# sar20-afbr-s50-array-board.net
KiCad netlist of a schematic drawn in Altium Designer
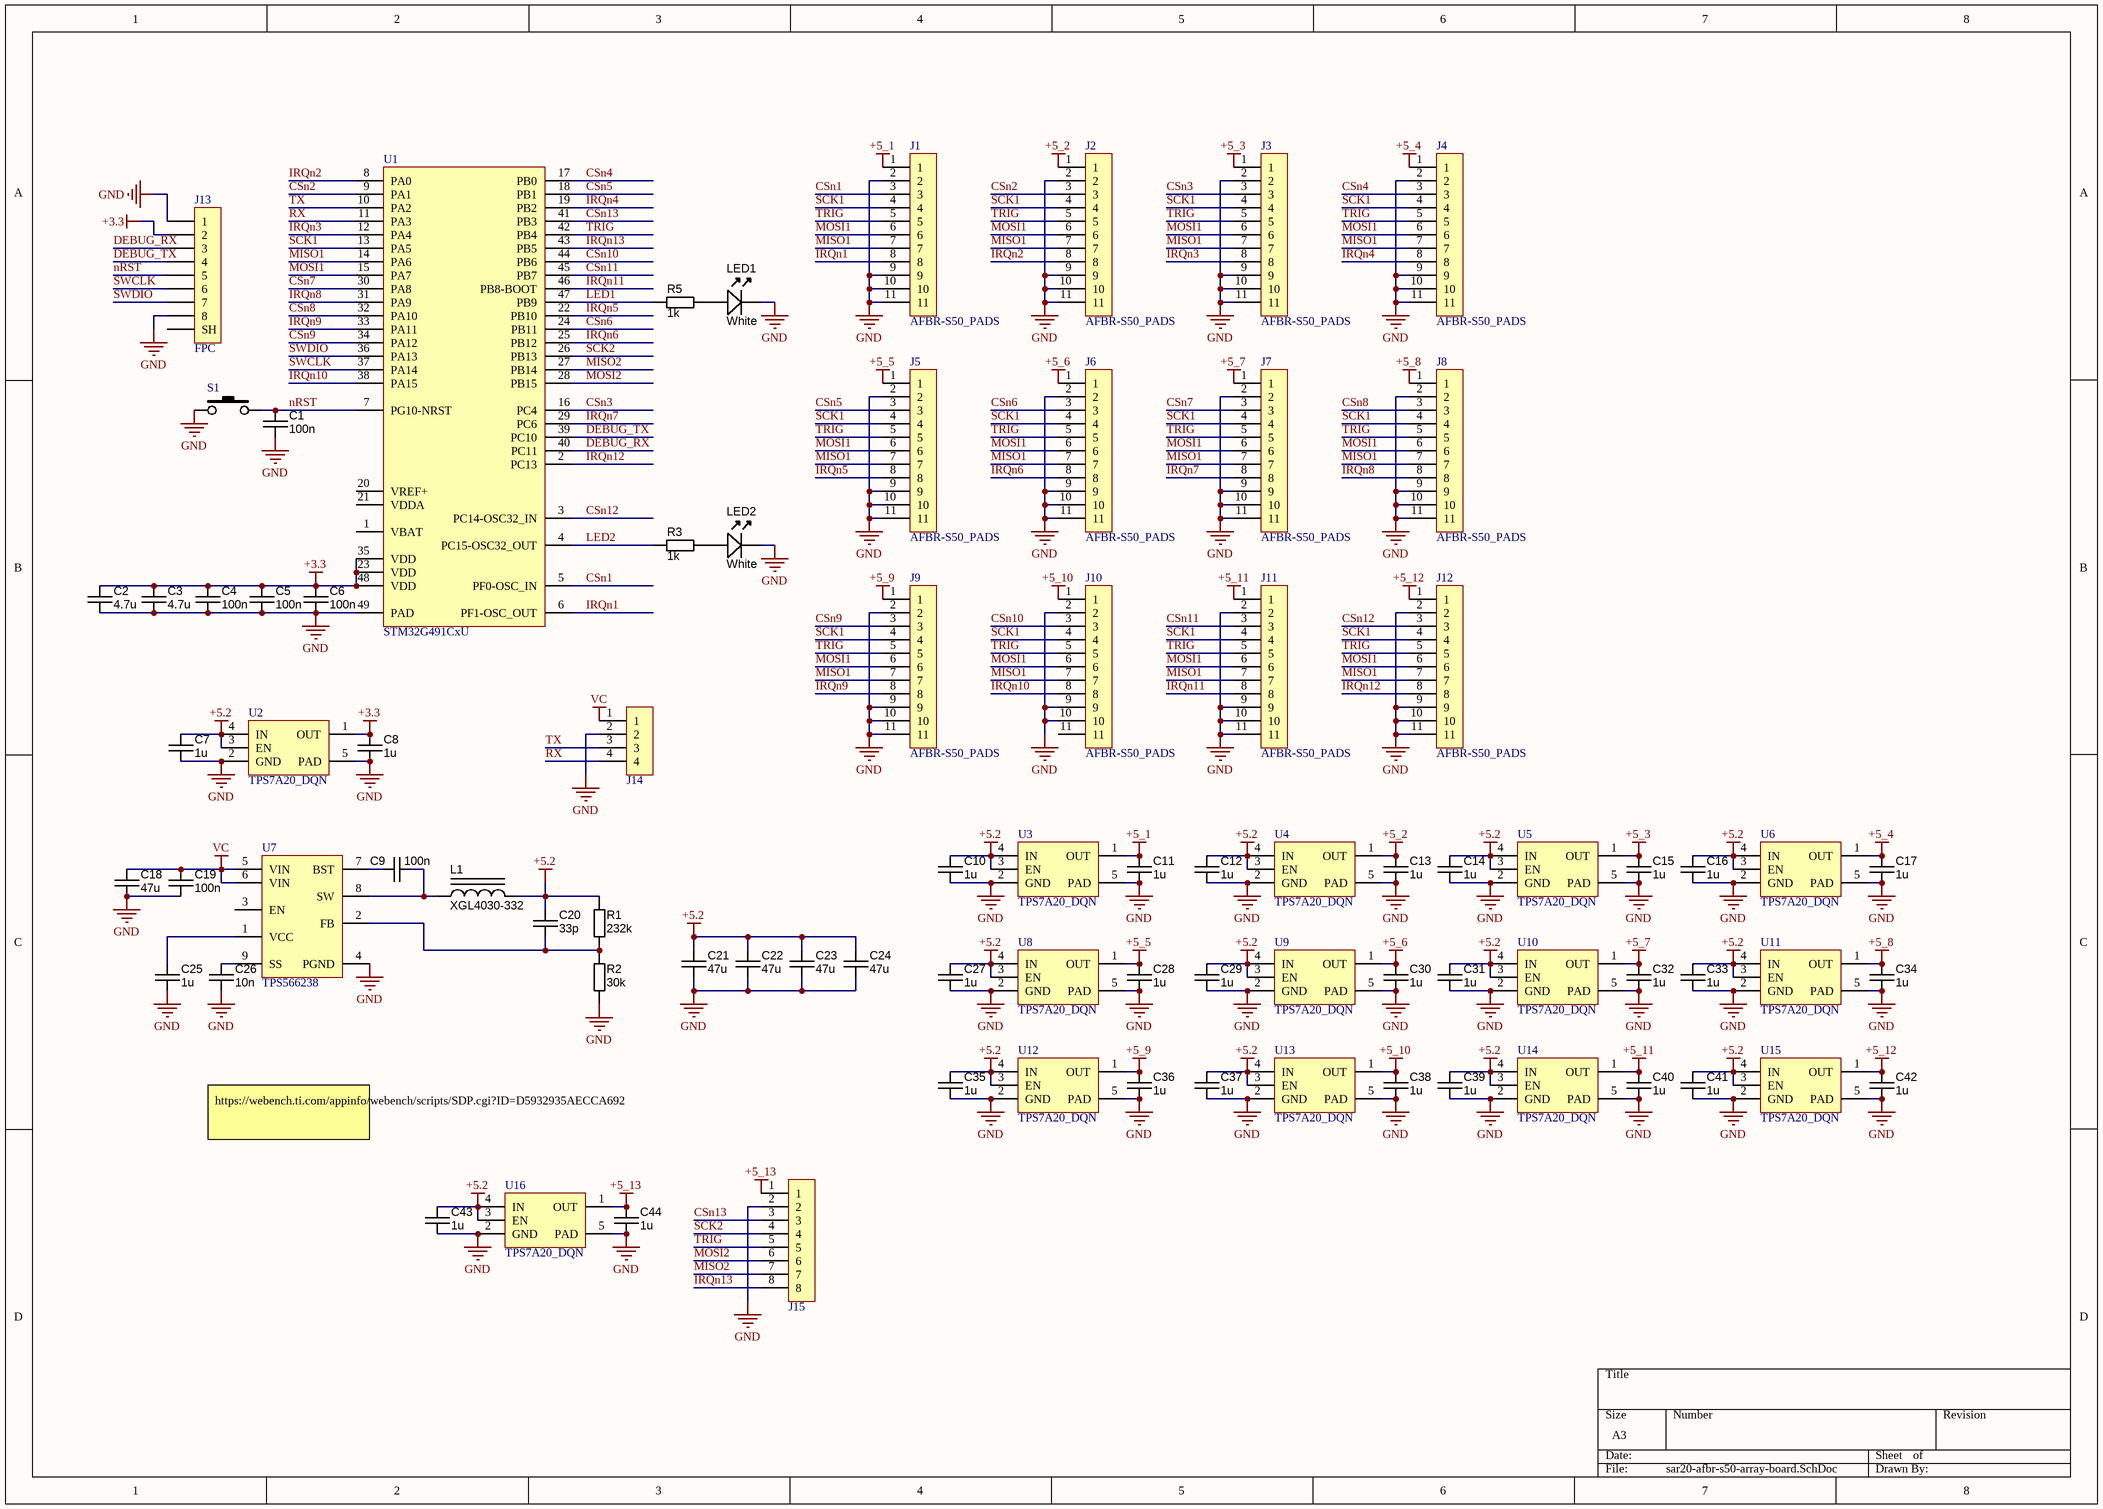
[diagram p0: sar20-afbr-s50-array-board.SchDoc]

(export (version "E")
  (design (tool "Eeschema 10.0.6"))
  (components
    (comp (ref "C1")
      (value "100n")
      (footprint "CAPC0603X04N")
      (fields (field (name "Comment") "CAPC_100n_0201"))
      (libsource (lib "passive") (part "CAPC_100n_0201"))
    )
    (comp (ref "C2")
      (value "4.7u")
      (footprint "CAPC1608X90N")
      (description "Capacitor SMD Cer 2.2uF 10% 10V X5R 0603")
      (fields (field (name "TOLERANCE") "±10%") (field (name "Comment") "approved sub OK"))
      (libsource (lib "PBL - Capacitors") (part "CAPC_2u2_0603_10V_10%"))
    )
    (comp (ref "C3")
      (value "4.7u")
      (footprint "CAPC1608X90N")
      (description "Capacitor SMD Cer 2.2uF 10% 10V X5R 0603")
      (fields (field (name "TOLERANCE") "±10%") (field (name "Comment") "approved sub OK"))
      (libsource (lib "PBL - Capacitors") (part "CAPC_2u2_0603_10V_10%"))
    )
    (comp (ref "C4")
      (value "100n")
      (footprint "CAPC1005X55N")
      (description "Capacitor SMD Cer 100nF 10% 16V X5R 0402")
      (fields (field (name "TOLERANCE") "±10%"))
      (libsource (lib "PBL - Capacitors") (part "CAPC_100n_0402_X5R_16V_10%"))
    )
    (comp (ref "C5")
      (value "100n")
      (footprint "CAPC1005X55N")
      (description "Capacitor SMD Cer 100nF 10% 16V X5R 0402")
      (fields (field (name "TOLERANCE") "±10%"))
      (libsource (lib "PBL - Capacitors") (part "CAPC_100n_0402_X5R_16V_10%"))
    )
    (comp (ref "C6")
      (value "100n")
      (footprint "CAPC1005X55N")
      (description "Capacitor SMD Cer 100nF 10% 16V X5R 0402")
      (fields (field (name "TOLERANCE") "±10%"))
      (libsource (lib "PBL - Capacitors") (part "CAPC_100n_0402_X5R_16V_10%"))
    )
    (comp (ref "C7")
      (value "1u")
      (footprint "CAPC1005X55N")
      (description "Capacitor SMD Cer 100nF 10% 16V X5R 0402")
      (fields (field (name "TOLERANCE") "±10%"))
      (libsource (lib "PBL - Capacitors") (part "CAPC_100n_0402_X5R_16V_10%"))
    )
    (comp (ref "C8")
      (value "1u")
      (footprint "CAPC1005X55N")
      (description "Capacitor SMD Cer 100nF 10% 16V X5R 0402")
      (fields (field (name "TOLERANCE") "±10%"))
      (libsource (lib "PBL - Capacitors") (part "CAPC_100n_0402_X5R_16V_10%"))
    )
    (comp (ref "C9")
      (value "100n")
      (footprint "CAPC1005X55N")
      (description "Capacitor SMD Cer 100nF 10% 16V X5R 0402")
      (fields (field (name "TOLERANCE") "±10%"))
      (libsource (lib "PBL - Capacitors") (part "CAPC_100n_0402_X5R_16V_10%"))
    )
    (comp (ref "C10")
      (value "1u")
      (footprint "CAPC1005X55N")
      (description "Capacitor SMD Cer 100nF 10% 16V X5R 0402")
      (fields (field (name "TOLERANCE") "±10%"))
      (libsource (lib "PBL - Capacitors") (part "CAPC_100n_0402_X5R_16V_10%"))
    )
    (comp (ref "C11")
      (value "1u")
      (footprint "CAPC1005X55N")
      (description "Capacitor SMD Cer 100nF 10% 16V X5R 0402")
      (fields (field (name "TOLERANCE") "±10%"))
      (libsource (lib "PBL - Capacitors") (part "CAPC_100n_0402_X5R_16V_10%"))
    )
    (comp (ref "C12")
      (value "1u")
      (footprint "CAPC1005X55N")
      (description "Capacitor SMD Cer 100nF 10% 16V X5R 0402")
      (fields (field (name "TOLERANCE") "±10%"))
      (libsource (lib "PBL - Capacitors") (part "CAPC_100n_0402_X5R_16V_10%"))
    )
    (comp (ref "C13")
      (value "1u")
      (footprint "CAPC1005X55N")
      (description "Capacitor SMD Cer 100nF 10% 16V X5R 0402")
      (fields (field (name "TOLERANCE") "±10%"))
      (libsource (lib "PBL - Capacitors") (part "CAPC_100n_0402_X5R_16V_10%"))
    )
    (comp (ref "C14")
      (value "1u")
      (footprint "CAPC1005X55N")
      (description "Capacitor SMD Cer 100nF 10% 16V X5R 0402")
      (fields (field (name "TOLERANCE") "±10%"))
      (libsource (lib "PBL - Capacitors") (part "CAPC_100n_0402_X5R_16V_10%"))
    )
    (comp (ref "C15")
      (value "1u")
      (footprint "CAPC1005X55N")
      (description "Capacitor SMD Cer 100nF 10% 16V X5R 0402")
      (fields (field (name "TOLERANCE") "±10%"))
      (libsource (lib "PBL - Capacitors") (part "CAPC_100n_0402_X5R_16V_10%"))
    )
    (comp (ref "C16")
      (value "1u")
      (footprint "CAPC1005X55N")
      (description "Capacitor SMD Cer 100nF 10% 16V X5R 0402")
      (fields (field (name "TOLERANCE") "±10%"))
      (libsource (lib "PBL - Capacitors") (part "CAPC_100n_0402_X5R_16V_10%"))
    )
    (comp (ref "C17")
      (value "1u")
      (footprint "CAPC1005X55N")
      (description "Capacitor SMD Cer 100nF 10% 16V X5R 0402")
      (fields (field (name "TOLERANCE") "±10%"))
      (libsource (lib "PBL - Capacitors") (part "CAPC_100n_0402_X5R_16V_10%"))
    )
    (comp (ref "C18")
      (value "47u")
      (footprint "CAPC3216X180N")
      (description "Capacitor SMD Cer 10uF 10% 16V X7R 1206")
      (fields (field (name "TOLERANCE") "±10%") (field (name "Comment") "approved sub OK"))
      (libsource (lib "PBL - Capacitors") (part "CAPC_10u_1206_16V"))
    )
    (comp (ref "C19")
      (value "100n")
      (footprint "CAPC1005X55N")
      (description "Capacitor SMD Cer 100nF 10% 16V X5R 0402")
      (fields (field (name "TOLERANCE") "±10%"))
      (libsource (lib "PBL - Capacitors") (part "CAPC_100n_0402_X5R_16V_10%"))
    )
    (comp (ref "C20")
      (value "33p")
      (footprint "CAPC1005X55N")
      (description "Capacitor SMD Cer 100nF 10% 16V X5R 0402")
      (fields (field (name "TOLERANCE") "±10%"))
      (libsource (lib "PBL - Capacitors") (part "CAPC_100n_0402_X5R_16V_10%"))
    )
    (comp (ref "C21")
      (value "47u")
      (footprint "CAPC3216X180N")
      (description "Capacitor SMD Cer 10uF 10% 16V X7R 1206")
      (fields (field (name "TOLERANCE") "±10%") (field (name "Comment") "approved sub OK"))
      (libsource (lib "PBL - Capacitors") (part "CAPC_10u_1206_16V"))
    )
    (comp (ref "C22")
      (value "47u")
      (footprint "CAPC3216X180N")
      (description "Capacitor SMD Cer 10uF 10% 16V X7R 1206")
      (fields (field (name "TOLERANCE") "±10%") (field (name "Comment") "approved sub OK"))
      (libsource (lib "PBL - Capacitors") (part "CAPC_10u_1206_16V"))
    )
    (comp (ref "C23")
      (value "47u")
      (footprint "CAPC3216X180N")
      (description "Capacitor SMD Cer 10uF 10% 16V X7R 1206")
      (fields (field (name "TOLERANCE") "±10%") (field (name "Comment") "approved sub OK"))
      (libsource (lib "PBL - Capacitors") (part "CAPC_10u_1206_16V"))
    )
    (comp (ref "C24")
      (value "47u")
      (footprint "CAPC3216X180N")
      (description "Capacitor SMD Cer 10uF 10% 16V X7R 1206")
      (fields (field (name "TOLERANCE") "±10%") (field (name "Comment") "approved sub OK"))
      (libsource (lib "PBL - Capacitors") (part "CAPC_10u_1206_16V"))
    )
    (comp (ref "C25")
      (value "1u")
      (footprint "CAPC1005X55N")
      (description "Capacitor SMD Cer 100nF 10% 16V X5R 0402")
      (fields (field (name "TOLERANCE") "±10%"))
      (libsource (lib "PBL - Capacitors") (part "CAPC_100n_0402_X5R_16V_10%"))
    )
    (comp (ref "C26")
      (value "10n")
      (footprint "CAPC1005X55N")
      (description "Capacitor SMD Cer 100nF 10% 16V X5R 0402")
      (fields (field (name "TOLERANCE") "±10%"))
      (libsource (lib "PBL - Capacitors") (part "CAPC_100n_0402_X5R_16V_10%"))
    )
    (comp (ref "C27")
      (value "1u")
      (footprint "CAPC1005X55N")
      (description "Capacitor SMD Cer 100nF 10% 16V X5R 0402")
      (fields (field (name "TOLERANCE") "±10%"))
      (libsource (lib "PBL - Capacitors") (part "CAPC_100n_0402_X5R_16V_10%"))
    )
    (comp (ref "C28")
      (value "1u")
      (footprint "CAPC1005X55N")
      (description "Capacitor SMD Cer 100nF 10% 16V X5R 0402")
      (fields (field (name "TOLERANCE") "±10%"))
      (libsource (lib "PBL - Capacitors") (part "CAPC_100n_0402_X5R_16V_10%"))
    )
    (comp (ref "C29")
      (value "1u")
      (footprint "CAPC1005X55N")
      (description "Capacitor SMD Cer 100nF 10% 16V X5R 0402")
      (fields (field (name "TOLERANCE") "±10%"))
      (libsource (lib "PBL - Capacitors") (part "CAPC_100n_0402_X5R_16V_10%"))
    )
    (comp (ref "C30")
      (value "1u")
      (footprint "CAPC1005X55N")
      (description "Capacitor SMD Cer 100nF 10% 16V X5R 0402")
      (fields (field (name "TOLERANCE") "±10%"))
      (libsource (lib "PBL - Capacitors") (part "CAPC_100n_0402_X5R_16V_10%"))
    )
    (comp (ref "C31")
      (value "1u")
      (footprint "CAPC1005X55N")
      (description "Capacitor SMD Cer 100nF 10% 16V X5R 0402")
      (fields (field (name "TOLERANCE") "±10%"))
      (libsource (lib "PBL - Capacitors") (part "CAPC_100n_0402_X5R_16V_10%"))
    )
    (comp (ref "C32")
      (value "1u")
      (footprint "CAPC1005X55N")
      (description "Capacitor SMD Cer 100nF 10% 16V X5R 0402")
      (fields (field (name "TOLERANCE") "±10%"))
      (libsource (lib "PBL - Capacitors") (part "CAPC_100n_0402_X5R_16V_10%"))
    )
    (comp (ref "C33")
      (value "1u")
      (footprint "CAPC1005X55N")
      (description "Capacitor SMD Cer 100nF 10% 16V X5R 0402")
      (fields (field (name "TOLERANCE") "±10%"))
      (libsource (lib "PBL - Capacitors") (part "CAPC_100n_0402_X5R_16V_10%"))
    )
    (comp (ref "C34")
      (value "1u")
      (footprint "CAPC1005X55N")
      (description "Capacitor SMD Cer 100nF 10% 16V X5R 0402")
      (fields (field (name "TOLERANCE") "±10%"))
      (libsource (lib "PBL - Capacitors") (part "CAPC_100n_0402_X5R_16V_10%"))
    )
    (comp (ref "C35")
      (value "1u")
      (footprint "CAPC1005X55N")
      (description "Capacitor SMD Cer 100nF 10% 16V X5R 0402")
      (fields (field (name "TOLERANCE") "±10%"))
      (libsource (lib "PBL - Capacitors") (part "CAPC_100n_0402_X5R_16V_10%"))
    )
    (comp (ref "C36")
      (value "1u")
      (footprint "CAPC1005X55N")
      (description "Capacitor SMD Cer 100nF 10% 16V X5R 0402")
      (fields (field (name "TOLERANCE") "±10%"))
      (libsource (lib "PBL - Capacitors") (part "CAPC_100n_0402_X5R_16V_10%"))
    )
    (comp (ref "C37")
      (value "1u")
      (footprint "CAPC1005X55N")
      (description "Capacitor SMD Cer 100nF 10% 16V X5R 0402")
      (fields (field (name "TOLERANCE") "±10%"))
      (libsource (lib "PBL - Capacitors") (part "CAPC_100n_0402_X5R_16V_10%"))
    )
    (comp (ref "C38")
      (value "1u")
      (footprint "CAPC1005X55N")
      (description "Capacitor SMD Cer 100nF 10% 16V X5R 0402")
      (fields (field (name "TOLERANCE") "±10%"))
      (libsource (lib "PBL - Capacitors") (part "CAPC_100n_0402_X5R_16V_10%"))
    )
    (comp (ref "C39")
      (value "1u")
      (footprint "CAPC1005X55N")
      (description "Capacitor SMD Cer 100nF 10% 16V X5R 0402")
      (fields (field (name "TOLERANCE") "±10%"))
      (libsource (lib "PBL - Capacitors") (part "CAPC_100n_0402_X5R_16V_10%"))
    )
    (comp (ref "C40")
      (value "1u")
      (footprint "CAPC1005X55N")
      (description "Capacitor SMD Cer 100nF 10% 16V X5R 0402")
      (fields (field (name "TOLERANCE") "±10%"))
      (libsource (lib "PBL - Capacitors") (part "CAPC_100n_0402_X5R_16V_10%"))
    )
    (comp (ref "C41")
      (value "1u")
      (footprint "CAPC1005X55N")
      (description "Capacitor SMD Cer 100nF 10% 16V X5R 0402")
      (fields (field (name "TOLERANCE") "±10%"))
      (libsource (lib "PBL - Capacitors") (part "CAPC_100n_0402_X5R_16V_10%"))
    )
    (comp (ref "C42")
      (value "1u")
      (footprint "CAPC1005X55N")
      (description "Capacitor SMD Cer 100nF 10% 16V X5R 0402")
      (fields (field (name "TOLERANCE") "±10%"))
      (libsource (lib "PBL - Capacitors") (part "CAPC_100n_0402_X5R_16V_10%"))
    )
    (comp (ref "C43")
      (value "1u")
      (footprint "CAPC1005X55N")
      (description "Capacitor SMD Cer 100nF 10% 16V X5R 0402")
      (fields (field (name "TOLERANCE") "±10%"))
      (libsource (lib "PBL - Capacitors") (part "CAPC_100n_0402_X5R_16V_10%"))
    )
    (comp (ref "C44")
      (value "1u")
      (footprint "CAPC1005X55N")
      (description "Capacitor SMD Cer 100nF 10% 16V X5R 0402")
      (fields (field (name "TOLERANCE") "±10%"))
      (libsource (lib "PBL - Capacitors") (part "CAPC_100n_0402_X5R_16V_10%"))
    )
    (comp (ref "J1")
      (value "AFBR-S50_PADS")
      (footprint "AFBR-S50_PADS")
      (libsource (lib "sar20-afbr-s50-array-board") (part "AFBR-S50_PADS"))
    )
    (comp (ref "J2")
      (value "AFBR-S50_PADS")
      (footprint "AFBR-S50_PADS")
      (libsource (lib "sar20-afbr-s50-array-board") (part "AFBR-S50_PADS"))
    )
    (comp (ref "J3")
      (value "AFBR-S50_PADS")
      (footprint "AFBR-S50_PADS")
      (libsource (lib "sar20-afbr-s50-array-board") (part "AFBR-S50_PADS"))
    )
    (comp (ref "J4")
      (value "AFBR-S50_PADS")
      (footprint "AFBR-S50_PADS")
      (libsource (lib "sar20-afbr-s50-array-board") (part "AFBR-S50_PADS"))
    )
    (comp (ref "J5")
      (value "AFBR-S50_PADS")
      (footprint "AFBR-S50_PADS")
      (libsource (lib "sar20-afbr-s50-array-board") (part "AFBR-S50_PADS"))
    )
    (comp (ref "J6")
      (value "AFBR-S50_PADS")
      (footprint "AFBR-S50_PADS")
      (libsource (lib "sar20-afbr-s50-array-board") (part "AFBR-S50_PADS"))
    )
    (comp (ref "J7")
      (value "AFBR-S50_PADS")
      (footprint "AFBR-S50_PADS")
      (libsource (lib "sar20-afbr-s50-array-board") (part "AFBR-S50_PADS"))
    )
    (comp (ref "J8")
      (value "AFBR-S50_PADS")
      (footprint "AFBR-S50_PADS")
      (libsource (lib "sar20-afbr-s50-array-board") (part "AFBR-S50_PADS"))
    )
    (comp (ref "J9")
      (value "AFBR-S50_PADS")
      (footprint "AFBR-S50_PADS")
      (libsource (lib "sar20-afbr-s50-array-board") (part "AFBR-S50_PADS"))
    )
    (comp (ref "J10")
      (value "AFBR-S50_PADS")
      (footprint "AFBR-S50_PADS")
      (libsource (lib "sar20-afbr-s50-array-board") (part "AFBR-S50_PADS"))
    )
    (comp (ref "J11")
      (value "AFBR-S50_PADS")
      (footprint "AFBR-S50_PADS")
      (libsource (lib "sar20-afbr-s50-array-board") (part "AFBR-S50_PADS"))
    )
    (comp (ref "J12")
      (value "AFBR-S50_PADS")
      (footprint "AFBR-S50_PADS")
      (libsource (lib "sar20-afbr-s50-array-board") (part "AFBR-S50_PADS"))
    )
    (comp (ref "J13")
      (value "FPC")
      (footprint "HIROSE-FH19C-8S-0.5SH")
      (libsource (lib "connectors") (part "FPC-CONNECTOR-8"))
    )
    (comp (ref "J14")
      (value "MOLEX_PICOBLADE_530470410")
      (footprint "MOLEX_PICOBLADE_530470410")
      (libsource (lib "connectors") (part "MOLEX_PICOBLADE_530470410"))
    )
    (comp (ref "J15")
      (value "MOLEX_PICOBLADE_532610871")
      (footprint "MOLEX_PICOBLADE_532610871")
      (libsource (lib "connectors") (part "MOLEX_PICOBLADE_532610871"))
    )
    (comp (ref "L1") (value "XGL4030-332") (footprint "XGL4030") (libsource (lib "passive") (part "XGL4030")))
    (comp (ref "LED1")
      (value "White")
      (footprint "LED-0603-WHITE")
      (description "LED 0603 SMD Bright White 8700K")
      (libsource (lib "PBL - Light Sources") (part "LED_SMD_White_0603_Bright"))
    )
    (comp (ref "LED2")
      (value "White")
      (footprint "LED-0603-WHITE")
      (description "LED 0603 SMD Bright White 8700K")
      (libsource (lib "PBL - Light Sources") (part "LED_SMD_White_0603_Bright"))
    )
    (comp (ref "R1")
      (value "232k")
      (footprint "RESC1005X40N")
      (description "Resistor SMD chip 10k Ohm 0.063W 1% 0402")
      (fields (field (name "TOLERANCE") "±1%") (field (name "Comment") "Thick Film"))
      (libsource (lib "PBL - Resistors") (part "RES_10K_0402_1%"))
    )
    (comp (ref "R2")
      (value "30k")
      (footprint "RESC1005X40N")
      (description "Resistor SMD chip 10k Ohm 0.063W 1% 0402")
      (fields (field (name "TOLERANCE") "±1%") (field (name "Comment") "Thick Film"))
      (libsource (lib "PBL - Resistors") (part "RES_10K_0402_1%"))
    )
    (comp (ref "R3")
      (value "1k")
      (footprint "RESC1005X40N")
      (description "Resistor SMD chip 1k Ohm 0.063W 5% 0402")
      (fields (field (name "TOLERANCE") "±5%") (field (name "Comment") "Thick Film"))
      (libsource (lib "PBL - Resistors") (part "RES_1K_0402_5%"))
    )
    (comp (ref "R5")
      (value "1k")
      (footprint "RESC1005X40N")
      (description "Resistor SMD chip 1k Ohm 0.063W 5% 0402")
      (fields (field (name "TOLERANCE") "±5%") (field (name "Comment") "Thick Film"))
      (libsource (lib "PBL - Resistors") (part "RES_1K_0402_5%"))
    )
    (comp (ref "S1")
      (value "PUSHBUTTON")
      (footprint "KMR421NGLFS")
      (libsource (lib "switches") (part "PUSHBUTTON"))
    )
    (comp (ref "U1")
      (value "STM32G491CxU")
      (footprint "QFN50P700X700X60_HS-49N")
      (libsource (lib "sar20-afbr-s50-array-board") (part "STM32G491CxU"))
    )
    (comp (ref "U2")
      (value "TPS7A20_DQN")
      (footprint "TI_X2SON_DQN0004A")
      (libsource (lib "texas_instruments") (part "TPS7A20_DQN"))
    )
    (comp (ref "U3")
      (value "TPS7A20_DQN")
      (footprint "TI_X2SON_DQN0004A")
      (libsource (lib "texas_instruments") (part "TPS7A20_DQN"))
    )
    (comp (ref "U4")
      (value "TPS7A20_DQN")
      (footprint "TI_X2SON_DQN0004A")
      (libsource (lib "texas_instruments") (part "TPS7A20_DQN"))
    )
    (comp (ref "U5")
      (value "TPS7A20_DQN")
      (footprint "TI_X2SON_DQN0004A")
      (libsource (lib "texas_instruments") (part "TPS7A20_DQN"))
    )
    (comp (ref "U6")
      (value "TPS7A20_DQN")
      (footprint "TI_X2SON_DQN0004A")
      (libsource (lib "texas_instruments") (part "TPS7A20_DQN"))
    )
    (comp (ref "U7")
      (value "TPS566238")
      (footprint "TI_VQFN-HR_RQF0009A")
      (libsource (lib "texas_instruments") (part "TPS566238"))
    )
    (comp (ref "U8")
      (value "TPS7A20_DQN")
      (footprint "TI_X2SON_DQN0004A")
      (libsource (lib "texas_instruments") (part "TPS7A20_DQN"))
    )
    (comp (ref "U9")
      (value "TPS7A20_DQN")
      (footprint "TI_X2SON_DQN0004A")
      (libsource (lib "texas_instruments") (part "TPS7A20_DQN"))
    )
    (comp (ref "U10")
      (value "TPS7A20_DQN")
      (footprint "TI_X2SON_DQN0004A")
      (libsource (lib "texas_instruments") (part "TPS7A20_DQN"))
    )
    (comp (ref "U11")
      (value "TPS7A20_DQN")
      (footprint "TI_X2SON_DQN0004A")
      (libsource (lib "texas_instruments") (part "TPS7A20_DQN"))
    )
    (comp (ref "U12")
      (value "TPS7A20_DQN")
      (footprint "TI_X2SON_DQN0004A")
      (libsource (lib "texas_instruments") (part "TPS7A20_DQN"))
    )
    (comp (ref "U13")
      (value "TPS7A20_DQN")
      (footprint "TI_X2SON_DQN0004A")
      (libsource (lib "texas_instruments") (part "TPS7A20_DQN"))
    )
    (comp (ref "U14")
      (value "TPS7A20_DQN")
      (footprint "TI_X2SON_DQN0004A")
      (libsource (lib "texas_instruments") (part "TPS7A20_DQN"))
    )
    (comp (ref "U15")
      (value "TPS7A20_DQN")
      (footprint "TI_X2SON_DQN0004A")
      (libsource (lib "texas_instruments") (part "TPS7A20_DQN"))
    )
    (comp (ref "U16")
      (value "TPS7A20_DQN")
      (footprint "TI_X2SON_DQN0004A")
      (libsource (lib "texas_instruments") (part "TPS7A20_DQN"))
    )
  )
  (nets
    (net (code "1") (name "+3.3") (class "Default")
      (node (ref "C2") (pin "1") (pintype "passive"))
      (node (ref "C3") (pin "1") (pintype "passive"))
      (node (ref "C4") (pin "2") (pintype "passive"))
      (node (ref "C5") (pin "2") (pintype "passive"))
      (node (ref "C6") (pin "2") (pintype "passive"))
      (node (ref "C8") (pin "2") (pintype "passive"))
      (node (ref "J13") (pin "2") (pinfunction "2_2") (pintype "passive"))
      (node (ref "U1") (pin "23") (pinfunction "VDD_23") (pintype "passive"))
      (node (ref "U1") (pin "35") (pinfunction "VDD_35") (pintype "passive"))
      (node (ref "U1") (pin "48") (pinfunction "VDD_48") (pintype "passive"))
      (node (ref "U2") (pin "1") (pinfunction "OUT_1") (pintype "passive"))
    )
    (net (code "2") (name "+5.2") (class "Default")
      (node (ref "C10") (pin "2") (pintype "passive"))
      (node (ref "C12") (pin "2") (pintype "passive"))
      (node (ref "C14") (pin "2") (pintype "passive"))
      (node (ref "C16") (pin "2") (pintype "passive"))
      (node (ref "C20") (pin "2") (pintype "passive"))
      (node (ref "C21") (pin "1") (pintype "passive"))
      (node (ref "C22") (pin "1") (pintype "passive"))
      (node (ref "C23") (pin "1") (pintype "passive"))
      (node (ref "C24") (pin "1") (pintype "passive"))
      (node (ref "C27") (pin "2") (pintype "passive"))
      (node (ref "C29") (pin "2") (pintype "passive"))
      (node (ref "C31") (pin "2") (pintype "passive"))
      (node (ref "C33") (pin "2") (pintype "passive"))
      (node (ref "C35") (pin "2") (pintype "passive"))
      (node (ref "C37") (pin "2") (pintype "passive"))
      (node (ref "C39") (pin "2") (pintype "passive"))
      (node (ref "C41") (pin "2") (pintype "passive"))
      (node (ref "C43") (pin "2") (pintype "passive"))
      (node (ref "C7") (pin "2") (pintype "passive"))
      (node (ref "L1") (pin "2") (pinfunction "2_2") (pintype "passive"))
      (node (ref "R1") (pin "2") (pinfunction "2_2") (pintype "passive"))
      (node (ref "U10") (pin "3") (pinfunction "EN_3") (pintype "passive"))
      (node (ref "U10") (pin "4") (pinfunction "IN_4") (pintype "passive"))
      (node (ref "U11") (pin "3") (pinfunction "EN_3") (pintype "passive"))
      (node (ref "U11") (pin "4") (pinfunction "IN_4") (pintype "passive"))
      (node (ref "U12") (pin "3") (pinfunction "EN_3") (pintype "passive"))
      (node (ref "U12") (pin "4") (pinfunction "IN_4") (pintype "passive"))
      (node (ref "U13") (pin "3") (pinfunction "EN_3") (pintype "passive"))
      (node (ref "U13") (pin "4") (pinfunction "IN_4") (pintype "passive"))
      (node (ref "U14") (pin "3") (pinfunction "EN_3") (pintype "passive"))
      (node (ref "U14") (pin "4") (pinfunction "IN_4") (pintype "passive"))
      (node (ref "U15") (pin "3") (pinfunction "EN_3") (pintype "passive"))
      (node (ref "U15") (pin "4") (pinfunction "IN_4") (pintype "passive"))
      (node (ref "U16") (pin "3") (pinfunction "EN_3") (pintype "passive"))
      (node (ref "U16") (pin "4") (pinfunction "IN_4") (pintype "passive"))
      (node (ref "U2") (pin "3") (pinfunction "EN_3") (pintype "passive"))
      (node (ref "U2") (pin "4") (pinfunction "IN_4") (pintype "passive"))
      (node (ref "U3") (pin "3") (pinfunction "EN_3") (pintype "passive"))
      (node (ref "U3") (pin "4") (pinfunction "IN_4") (pintype "passive"))
      (node (ref "U4") (pin "3") (pinfunction "EN_3") (pintype "passive"))
      (node (ref "U4") (pin "4") (pinfunction "IN_4") (pintype "passive"))
      (node (ref "U5") (pin "3") (pinfunction "EN_3") (pintype "passive"))
      (node (ref "U5") (pin "4") (pinfunction "IN_4") (pintype "passive"))
      (node (ref "U6") (pin "3") (pinfunction "EN_3") (pintype "passive"))
      (node (ref "U6") (pin "4") (pinfunction "IN_4") (pintype "passive"))
      (node (ref "U8") (pin "3") (pinfunction "EN_3") (pintype "passive"))
      (node (ref "U8") (pin "4") (pinfunction "IN_4") (pintype "passive"))
      (node (ref "U9") (pin "3") (pinfunction "EN_3") (pintype "passive"))
      (node (ref "U9") (pin "4") (pinfunction "IN_4") (pintype "passive"))
    )
    (net (code "3") (name "+5_1") (class "Default")
      (node (ref "C11") (pin "2") (pintype "passive"))
      (node (ref "J1") (pin "1") (pinfunction "1_1") (pintype "passive"))
      (node (ref "U3") (pin "1") (pinfunction "OUT_1") (pintype "passive"))
    )
    (net (code "4") (name "+5_2") (class "Default")
      (node (ref "C13") (pin "2") (pintype "passive"))
      (node (ref "J2") (pin "1") (pinfunction "1_1") (pintype "passive"))
      (node (ref "U4") (pin "1") (pinfunction "OUT_1") (pintype "passive"))
    )
    (net (code "5") (name "+5_3") (class "Default")
      (node (ref "C15") (pin "2") (pintype "passive"))
      (node (ref "J3") (pin "1") (pinfunction "1_1") (pintype "passive"))
      (node (ref "U5") (pin "1") (pinfunction "OUT_1") (pintype "passive"))
    )
    (net (code "6") (name "+5_4") (class "Default")
      (node (ref "C17") (pin "2") (pintype "passive"))
      (node (ref "J4") (pin "1") (pinfunction "1_1") (pintype "passive"))
      (node (ref "U6") (pin "1") (pinfunction "OUT_1") (pintype "passive"))
    )
    (net (code "7") (name "+5_5") (class "Default")
      (node (ref "C28") (pin "2") (pintype "passive"))
      (node (ref "J5") (pin "1") (pinfunction "1_1") (pintype "passive"))
      (node (ref "U8") (pin "1") (pinfunction "OUT_1") (pintype "passive"))
    )
    (net (code "8") (name "+5_6") (class "Default")
      (node (ref "C30") (pin "2") (pintype "passive"))
      (node (ref "J6") (pin "1") (pinfunction "1_1") (pintype "passive"))
      (node (ref "U9") (pin "1") (pinfunction "OUT_1") (pintype "passive"))
    )
    (net (code "9") (name "+5_7") (class "Default")
      (node (ref "C32") (pin "2") (pintype "passive"))
      (node (ref "J7") (pin "1") (pinfunction "1_1") (pintype "passive"))
      (node (ref "U10") (pin "1") (pinfunction "OUT_1") (pintype "passive"))
    )
    (net (code "10") (name "+5_8") (class "Default")
      (node (ref "C34") (pin "2") (pintype "passive"))
      (node (ref "J8") (pin "1") (pinfunction "1_1") (pintype "passive"))
      (node (ref "U11") (pin "1") (pinfunction "OUT_1") (pintype "passive"))
    )
    (net (code "11") (name "+5_9") (class "Default")
      (node (ref "C36") (pin "2") (pintype "passive"))
      (node (ref "J9") (pin "1") (pinfunction "1_1") (pintype "passive"))
      (node (ref "U12") (pin "1") (pinfunction "OUT_1") (pintype "passive"))
    )
    (net (code "12") (name "+5_10") (class "Default")
      (node (ref "C38") (pin "2") (pintype "passive"))
      (node (ref "J10") (pin "1") (pinfunction "1_1") (pintype "passive"))
      (node (ref "U13") (pin "1") (pinfunction "OUT_1") (pintype "passive"))
    )
    (net (code "13") (name "+5_11") (class "Default")
      (node (ref "C40") (pin "2") (pintype "passive"))
      (node (ref "J11") (pin "1") (pinfunction "1_1") (pintype "passive"))
      (node (ref "U14") (pin "1") (pinfunction "OUT_1") (pintype "passive"))
    )
    (net (code "14") (name "+5_12") (class "Default")
      (node (ref "C42") (pin "2") (pintype "passive"))
      (node (ref "J12") (pin "1") (pinfunction "1_1") (pintype "passive"))
      (node (ref "U15") (pin "1") (pinfunction "OUT_1") (pintype "passive"))
    )
    (net (code "15") (name "+5_13") (class "Default")
      (node (ref "C44") (pin "2") (pintype "passive"))
      (node (ref "J15") (pin "1") (pinfunction "1_1") (pintype "passive"))
      (node (ref "U16") (pin "1") (pinfunction "OUT_1") (pintype "passive"))
    )
    (net (code "16") (name "/CSn1") (class "Default")
      (node (ref "J1") (pin "3") (pinfunction "3_3") (pintype "passive"))
      (node (ref "U1") (pin "5") (pinfunction "PF0-OSC_IN_5") (pintype "passive"))
    )
    (net (code "17") (name "/CSn2") (class "Default")
      (node (ref "J2") (pin "3") (pinfunction "3_3") (pintype "passive"))
      (node (ref "U1") (pin "9") (pinfunction "PA1_9") (pintype "passive"))
    )
    (net (code "18") (name "/CSn3") (class "Default")
      (node (ref "J3") (pin "3") (pinfunction "3_3") (pintype "passive"))
      (node (ref "U1") (pin "16") (pinfunction "PC4_16") (pintype "passive"))
    )
    (net (code "19") (name "/CSn4") (class "Default")
      (node (ref "J4") (pin "3") (pinfunction "3_3") (pintype "passive"))
      (node (ref "U1") (pin "17") (pinfunction "PB0_17") (pintype "passive"))
    )
    (net (code "20") (name "/CSn5") (class "Default")
      (node (ref "J5") (pin "3") (pinfunction "3_3") (pintype "passive"))
      (node (ref "U1") (pin "18") (pinfunction "PB1_18") (pintype "passive"))
    )
    (net (code "21") (name "/CSn6") (class "Default")
      (node (ref "J6") (pin "3") (pinfunction "3_3") (pintype "passive"))
      (node (ref "U1") (pin "24") (pinfunction "PB11_24") (pintype "passive"))
    )
    (net (code "22") (name "/CSn7") (class "Default")
      (node (ref "J7") (pin "3") (pinfunction "3_3") (pintype "passive"))
      (node (ref "U1") (pin "30") (pinfunction "PA8_30") (pintype "passive"))
    )
    (net (code "23") (name "/CSn8") (class "Default")
      (node (ref "J8") (pin "3") (pinfunction "3_3") (pintype "passive"))
      (node (ref "U1") (pin "32") (pinfunction "PA10_32") (pintype "passive"))
    )
    (net (code "24") (name "/CSn9") (class "Default")
      (node (ref "J9") (pin "3") (pinfunction "3_3") (pintype "passive"))
      (node (ref "U1") (pin "34") (pinfunction "PA12_34") (pintype "passive"))
    )
    (net (code "25") (name "/CSn10") (class "Default")
      (node (ref "J10") (pin "3") (pinfunction "3_3") (pintype "passive"))
      (node (ref "U1") (pin "44") (pinfunction "PB6_44") (pintype "passive"))
    )
    (net (code "26") (name "/CSn11") (class "Default")
      (node (ref "J11") (pin "3") (pinfunction "3_3") (pintype "passive"))
      (node (ref "U1") (pin "45") (pinfunction "PB7_45") (pintype "passive"))
    )
    (net (code "27") (name "/CSn12") (class "Default")
      (node (ref "J12") (pin "3") (pinfunction "3_3") (pintype "passive"))
      (node (ref "U1") (pin "3") (pinfunction "PC14-OSC32_IN_3") (pintype "passive"))
    )
    (net (code "28") (name "/CSn13") (class "Default")
      (node (ref "J15") (pin "3") (pinfunction "3_3") (pintype "passive"))
      (node (ref "U1") (pin "41") (pinfunction "PB3_41") (pintype "passive"))
    )
    (net (code "29") (name "/DEBUG_RX") (class "Default")
      (node (ref "J13") (pin "3") (pinfunction "3_3") (pintype "passive"))
      (node (ref "U1") (pin "40") (pinfunction "PC11_40") (pintype "passive"))
    )
    (net (code "30") (name "/DEBUG_TX") (class "Default")
      (node (ref "J13") (pin "4") (pinfunction "4_4") (pintype "passive"))
      (node (ref "U1") (pin "39") (pinfunction "PC10_39") (pintype "passive"))
    )
    (net (code "31") (name "/IRQn1") (class "Default")
      (node (ref "J1") (pin "8") (pinfunction "8_8") (pintype "passive"))
      (node (ref "U1") (pin "6") (pinfunction "PF1-OSC_OUT_6") (pintype "passive"))
    )
    (net (code "32") (name "/IRQn2") (class "Default")
      (node (ref "J2") (pin "8") (pinfunction "8_8") (pintype "passive"))
      (node (ref "U1") (pin "8") (pinfunction "PA0_8") (pintype "passive"))
    )
    (net (code "33") (name "/IRQn3") (class "Default")
      (node (ref "J3") (pin "8") (pinfunction "8_8") (pintype "passive"))
      (node (ref "U1") (pin "12") (pinfunction "PA4_12") (pintype "passive"))
    )
    (net (code "34") (name "/IRQn4") (class "Default")
      (node (ref "J4") (pin "8") (pinfunction "8_8") (pintype "passive"))
      (node (ref "U1") (pin "19") (pinfunction "PB2_19") (pintype "passive"))
    )
    (net (code "35") (name "/IRQn5") (class "Default")
      (node (ref "J5") (pin "8") (pinfunction "8_8") (pintype "passive"))
      (node (ref "U1") (pin "22") (pinfunction "PB10_22") (pintype "passive"))
    )
    (net (code "36") (name "/IRQn6") (class "Default")
      (node (ref "J6") (pin "8") (pinfunction "8_8") (pintype "passive"))
      (node (ref "U1") (pin "25") (pinfunction "PB12_25") (pintype "passive"))
    )
    (net (code "37") (name "/IRQn7") (class "Default")
      (node (ref "J7") (pin "8") (pinfunction "8_8") (pintype "passive"))
      (node (ref "U1") (pin "29") (pinfunction "PC6_29") (pintype "passive"))
    )
    (net (code "38") (name "/IRQn8") (class "Default")
      (node (ref "J8") (pin "8") (pinfunction "8_8") (pintype "passive"))
      (node (ref "U1") (pin "31") (pinfunction "PA9_31") (pintype "passive"))
    )
    (net (code "39") (name "/IRQn9") (class "Default")
      (node (ref "J9") (pin "8") (pinfunction "8_8") (pintype "passive"))
      (node (ref "U1") (pin "33") (pinfunction "PA11_33") (pintype "passive"))
    )
    (net (code "40") (name "/IRQn10") (class "Default")
      (node (ref "J10") (pin "8") (pinfunction "8_8") (pintype "passive"))
      (node (ref "U1") (pin "38") (pinfunction "PA15_38") (pintype "passive"))
    )
    (net (code "41") (name "/IRQn11") (class "Default")
      (node (ref "J11") (pin "8") (pinfunction "8_8") (pintype "passive"))
      (node (ref "U1") (pin "46") (pinfunction "PB8-BOOT_46") (pintype "passive"))
    )
    (net (code "42") (name "/IRQn12") (class "Default")
      (node (ref "J12") (pin "8") (pinfunction "8_8") (pintype "passive"))
      (node (ref "U1") (pin "2") (pinfunction "PC13_2") (pintype "passive"))
    )
    (net (code "43") (name "/IRQn13") (class "Default")
      (node (ref "J15") (pin "8") (pinfunction "8_8") (pintype "passive"))
      (node (ref "U1") (pin "43") (pinfunction "PB5_43") (pintype "passive"))
    )
    (net (code "44") (name "/LED1") (class "Default")
      (node (ref "R5") (pin "1") (pinfunction "1_1") (pintype "passive"))
      (node (ref "U1") (pin "47") (pinfunction "PB9_47") (pintype "passive"))
    )
    (net (code "45") (name "/LED2") (class "Default")
      (node (ref "R3") (pin "1") (pinfunction "1_1") (pintype "passive"))
      (node (ref "U1") (pin "4") (pinfunction "PC15-OSC32_OUT_4") (pintype "passive"))
    )
    (net (code "46") (name "/MISO1") (class "Default")
      (node (ref "J1") (pin "7") (pinfunction "7_7") (pintype "passive"))
      (node (ref "J10") (pin "7") (pinfunction "7_7") (pintype "passive"))
      (node (ref "J11") (pin "7") (pinfunction "7_7") (pintype "passive"))
      (node (ref "J12") (pin "7") (pinfunction "7_7") (pintype "passive"))
      (node (ref "J2") (pin "7") (pinfunction "7_7") (pintype "passive"))
      (node (ref "J3") (pin "7") (pinfunction "7_7") (pintype "passive"))
      (node (ref "J4") (pin "7") (pinfunction "7_7") (pintype "passive"))
      (node (ref "J5") (pin "7") (pinfunction "7_7") (pintype "passive"))
      (node (ref "J6") (pin "7") (pinfunction "7_7") (pintype "passive"))
      (node (ref "J7") (pin "7") (pinfunction "7_7") (pintype "passive"))
      (node (ref "J8") (pin "7") (pinfunction "7_7") (pintype "passive"))
      (node (ref "J9") (pin "7") (pinfunction "7_7") (pintype "passive"))
      (node (ref "U1") (pin "14") (pinfunction "PA6_14") (pintype "passive"))
    )
    (net (code "47") (name "/MISO2") (class "Default")
      (node (ref "J15") (pin "7") (pinfunction "7_7") (pintype "passive"))
      (node (ref "U1") (pin "27") (pinfunction "PB14_27") (pintype "passive"))
    )
    (net (code "48") (name "/MOSI1") (class "Default")
      (node (ref "J1") (pin "6") (pinfunction "6_6") (pintype "passive"))
      (node (ref "J10") (pin "6") (pinfunction "6_6") (pintype "passive"))
      (node (ref "J11") (pin "6") (pinfunction "6_6") (pintype "passive"))
      (node (ref "J12") (pin "6") (pinfunction "6_6") (pintype "passive"))
      (node (ref "J2") (pin "6") (pinfunction "6_6") (pintype "passive"))
      (node (ref "J3") (pin "6") (pinfunction "6_6") (pintype "passive"))
      (node (ref "J4") (pin "6") (pinfunction "6_6") (pintype "passive"))
      (node (ref "J5") (pin "6") (pinfunction "6_6") (pintype "passive"))
      (node (ref "J6") (pin "6") (pinfunction "6_6") (pintype "passive"))
      (node (ref "J7") (pin "6") (pinfunction "6_6") (pintype "passive"))
      (node (ref "J8") (pin "6") (pinfunction "6_6") (pintype "passive"))
      (node (ref "J9") (pin "6") (pinfunction "6_6") (pintype "passive"))
      (node (ref "U1") (pin "15") (pinfunction "PA7_15") (pintype "passive"))
    )
    (net (code "49") (name "/MOSI2") (class "Default")
      (node (ref "J15") (pin "6") (pinfunction "6_6") (pintype "passive"))
      (node (ref "U1") (pin "28") (pinfunction "PB15_28") (pintype "passive"))
    )
    (net (code "50") (name "/RX") (class "Default")
      (node (ref "J14") (pin "4") (pinfunction "4_4") (pintype "passive"))
      (node (ref "U1") (pin "11") (pinfunction "PA3_11") (pintype "passive"))
    )
    (net (code "51") (name "/SCK1") (class "Default")
      (node (ref "J1") (pin "4") (pinfunction "4_4") (pintype "passive"))
      (node (ref "J10") (pin "4") (pinfunction "4_4") (pintype "passive"))
      (node (ref "J11") (pin "4") (pinfunction "4_4") (pintype "passive"))
      (node (ref "J12") (pin "4") (pinfunction "4_4") (pintype "passive"))
      (node (ref "J2") (pin "4") (pinfunction "4_4") (pintype "passive"))
      (node (ref "J3") (pin "4") (pinfunction "4_4") (pintype "passive"))
      (node (ref "J4") (pin "4") (pinfunction "4_4") (pintype "passive"))
      (node (ref "J5") (pin "4") (pinfunction "4_4") (pintype "passive"))
      (node (ref "J6") (pin "4") (pinfunction "4_4") (pintype "passive"))
      (node (ref "J7") (pin "4") (pinfunction "4_4") (pintype "passive"))
      (node (ref "J8") (pin "4") (pinfunction "4_4") (pintype "passive"))
      (node (ref "J9") (pin "4") (pinfunction "4_4") (pintype "passive"))
      (node (ref "U1") (pin "13") (pinfunction "PA5_13") (pintype "passive"))
    )
    (net (code "52") (name "/SCK2") (class "Default")
      (node (ref "J15") (pin "4") (pinfunction "4_4") (pintype "passive"))
      (node (ref "U1") (pin "26") (pinfunction "PB13_26") (pintype "passive"))
    )
    (net (code "53") (name "/SWCLK") (class "Default")
      (node (ref "J13") (pin "6") (pinfunction "6_6") (pintype "passive"))
      (node (ref "U1") (pin "37") (pinfunction "PA14_37") (pintype "passive"))
    )
    (net (code "54") (name "/SWDIO") (class "Default")
      (node (ref "J13") (pin "7") (pinfunction "7_7") (pintype "passive"))
      (node (ref "U1") (pin "36") (pinfunction "PA13_36") (pintype "passive"))
    )
    (net (code "55") (name "/TRIG") (class "Default")
      (node (ref "J1") (pin "5") (pinfunction "5_5") (pintype "passive"))
      (node (ref "J10") (pin "5") (pinfunction "5_5") (pintype "passive"))
      (node (ref "J11") (pin "5") (pinfunction "5_5") (pintype "passive"))
      (node (ref "J12") (pin "5") (pinfunction "5_5") (pintype "passive"))
      (node (ref "J15") (pin "5") (pinfunction "5_5") (pintype "passive"))
      (node (ref "J2") (pin "5") (pinfunction "5_5") (pintype "passive"))
      (node (ref "J3") (pin "5") (pinfunction "5_5") (pintype "passive"))
      (node (ref "J4") (pin "5") (pinfunction "5_5") (pintype "passive"))
      (node (ref "J5") (pin "5") (pinfunction "5_5") (pintype "passive"))
      (node (ref "J6") (pin "5") (pinfunction "5_5") (pintype "passive"))
      (node (ref "J7") (pin "5") (pinfunction "5_5") (pintype "passive"))
      (node (ref "J8") (pin "5") (pinfunction "5_5") (pintype "passive"))
      (node (ref "J9") (pin "5") (pinfunction "5_5") (pintype "passive"))
      (node (ref "U1") (pin "42") (pinfunction "PB4_42") (pintype "passive"))
    )
    (net (code "56") (name "/TX") (class "Default")
      (node (ref "J14") (pin "3") (pinfunction "3_3") (pintype "passive"))
      (node (ref "U1") (pin "10") (pinfunction "PA2_10") (pintype "passive"))
    )
    (net (code "57") (name "/nRST") (class "Default")
      (node (ref "C1") (pin "2") (pinfunction "2_2") (pintype "passive"))
      (node (ref "J13") (pin "5") (pinfunction "5_5") (pintype "passive"))
      (node (ref "S1") (pin "2") (pintype "passive"))
      (node (ref "U1") (pin "7") (pinfunction "PG10-NRST_7") (pintype "passive"))
    )
    (net (code "58") (name "GND") (class "Default")
      (node (ref "C1") (pin "1") (pinfunction "1_1") (pintype "passive"))
      (node (ref "C10") (pin "1") (pintype "passive"))
      (node (ref "C11") (pin "1") (pintype "passive"))
      (node (ref "C12") (pin "1") (pintype "passive"))
      (node (ref "C13") (pin "1") (pintype "passive"))
      (node (ref "C14") (pin "1") (pintype "passive"))
      (node (ref "C15") (pin "1") (pintype "passive"))
      (node (ref "C16") (pin "1") (pintype "passive"))
      (node (ref "C17") (pin "1") (pintype "passive"))
      (node (ref "C18") (pin "2") (pintype "passive"))
      (node (ref "C19") (pin "1") (pintype "passive"))
      (node (ref "C2") (pin "2") (pintype "passive"))
      (node (ref "C21") (pin "2") (pintype "passive"))
      (node (ref "C22") (pin "2") (pintype "passive"))
      (node (ref "C23") (pin "2") (pintype "passive"))
      (node (ref "C24") (pin "2") (pintype "passive"))
      (node (ref "C25") (pin "1") (pintype "passive"))
      (node (ref "C26") (pin "1") (pintype "passive"))
      (node (ref "C27") (pin "1") (pintype "passive"))
      (node (ref "C28") (pin "1") (pintype "passive"))
      (node (ref "C29") (pin "1") (pintype "passive"))
      (node (ref "C3") (pin "2") (pintype "passive"))
      (node (ref "C30") (pin "1") (pintype "passive"))
      (node (ref "C31") (pin "1") (pintype "passive"))
      (node (ref "C32") (pin "1") (pintype "passive"))
      (node (ref "C33") (pin "1") (pintype "passive"))
      (node (ref "C34") (pin "1") (pintype "passive"))
      (node (ref "C35") (pin "1") (pintype "passive"))
      (node (ref "C36") (pin "1") (pintype "passive"))
      (node (ref "C37") (pin "1") (pintype "passive"))
      (node (ref "C38") (pin "1") (pintype "passive"))
      (node (ref "C39") (pin "1") (pintype "passive"))
      (node (ref "C4") (pin "1") (pintype "passive"))
      (node (ref "C40") (pin "1") (pintype "passive"))
      (node (ref "C41") (pin "1") (pintype "passive"))
      (node (ref "C42") (pin "1") (pintype "passive"))
      (node (ref "C43") (pin "1") (pintype "passive"))
      (node (ref "C44") (pin "1") (pintype "passive"))
      (node (ref "C5") (pin "1") (pintype "passive"))
      (node (ref "C6") (pin "1") (pintype "passive"))
      (node (ref "C7") (pin "1") (pintype "passive"))
      (node (ref "C8") (pin "1") (pintype "passive"))
      (node (ref "J1") (pin "10") (pinfunction "10_10") (pintype "passive"))
      (node (ref "J1") (pin "11") (pinfunction "11_11") (pintype "passive"))
      (node (ref "J1") (pin "2") (pinfunction "2_2") (pintype "passive"))
      (node (ref "J1") (pin "9") (pinfunction "9_9") (pintype "passive"))
      (node (ref "J10") (pin "10") (pinfunction "10_10") (pintype "passive"))
      (node (ref "J10") (pin "2") (pinfunction "2_2") (pintype "passive"))
      (node (ref "J10") (pin "9") (pinfunction "9_9") (pintype "passive"))
      (node (ref "J11") (pin "10") (pinfunction "10_10") (pintype "passive"))
      (node (ref "J11") (pin "11") (pinfunction "11_11") (pintype "passive"))
      (node (ref "J11") (pin "2") (pinfunction "2_2") (pintype "passive"))
      (node (ref "J11") (pin "9") (pinfunction "9_9") (pintype "passive"))
      (node (ref "J12") (pin "10") (pinfunction "10_10") (pintype "passive"))
      (node (ref "J12") (pin "11") (pinfunction "11_11") (pintype "passive"))
      (node (ref "J12") (pin "2") (pinfunction "2_2") (pintype "passive"))
      (node (ref "J12") (pin "9") (pinfunction "9_9") (pintype "passive"))
      (node (ref "J13") (pin "1") (pinfunction "1_1") (pintype "passive"))
      (node (ref "J13") (pin "8") (pinfunction "8_8") (pintype "passive"))
      (node (ref "J14") (pin "2") (pinfunction "2_2") (pintype "passive"))
      (node (ref "J15") (pin "2") (pinfunction "2_2") (pintype "passive"))
      (node (ref "J2") (pin "10") (pinfunction "10_10") (pintype "passive"))
      (node (ref "J2") (pin "11") (pinfunction "11_11") (pintype "passive"))
      (node (ref "J2") (pin "2") (pinfunction "2_2") (pintype "passive"))
      (node (ref "J2") (pin "9") (pinfunction "9_9") (pintype "passive"))
      (node (ref "J3") (pin "10") (pinfunction "10_10") (pintype "passive"))
      (node (ref "J3") (pin "11") (pinfunction "11_11") (pintype "passive"))
      (node (ref "J3") (pin "2") (pinfunction "2_2") (pintype "passive"))
      (node (ref "J3") (pin "9") (pinfunction "9_9") (pintype "passive"))
      (node (ref "J4") (pin "10") (pinfunction "10_10") (pintype "passive"))
      (node (ref "J4") (pin "11") (pinfunction "11_11") (pintype "passive"))
      (node (ref "J4") (pin "2") (pinfunction "2_2") (pintype "passive"))
      (node (ref "J4") (pin "9") (pinfunction "9_9") (pintype "passive"))
      (node (ref "J5") (pin "10") (pinfunction "10_10") (pintype "passive"))
      (node (ref "J5") (pin "11") (pinfunction "11_11") (pintype "passive"))
      (node (ref "J5") (pin "2") (pinfunction "2_2") (pintype "passive"))
      (node (ref "J5") (pin "9") (pinfunction "9_9") (pintype "passive"))
      (node (ref "J6") (pin "10") (pinfunction "10_10") (pintype "passive"))
      (node (ref "J6") (pin "11") (pinfunction "11_11") (pintype "passive"))
      (node (ref "J6") (pin "2") (pinfunction "2_2") (pintype "passive"))
      (node (ref "J6") (pin "9") (pinfunction "9_9") (pintype "passive"))
      (node (ref "J7") (pin "10") (pinfunction "10_10") (pintype "passive"))
      (node (ref "J7") (pin "11") (pinfunction "11_11") (pintype "passive"))
      (node (ref "J7") (pin "2") (pinfunction "2_2") (pintype "passive"))
      (node (ref "J7") (pin "9") (pinfunction "9_9") (pintype "passive"))
      (node (ref "J8") (pin "10") (pinfunction "10_10") (pintype "passive"))
      (node (ref "J8") (pin "11") (pinfunction "11_11") (pintype "passive"))
      (node (ref "J8") (pin "2") (pinfunction "2_2") (pintype "passive"))
      (node (ref "J8") (pin "9") (pinfunction "9_9") (pintype "passive"))
      (node (ref "J9") (pin "10") (pinfunction "10_10") (pintype "passive"))
      (node (ref "J9") (pin "11") (pinfunction "11_11") (pintype "passive"))
      (node (ref "J9") (pin "2") (pinfunction "2_2") (pintype "passive"))
      (node (ref "J9") (pin "9") (pinfunction "9_9") (pintype "passive"))
      (node (ref "LED1") (pin "K") (pinfunction "K_K") (pintype "passive"))
      (node (ref "LED2") (pin "K") (pinfunction "K_K") (pintype "passive"))
      (node (ref "R2") (pin "1") (pinfunction "1_1") (pintype "passive"))
      (node (ref "S1") (pin "1") (pintype "passive"))
      (node (ref "U1") (pin "49") (pinfunction "PAD_49") (pintype "passive"))
      (node (ref "U10") (pin "2") (pinfunction "GND_2") (pintype "passive"))
      (node (ref "U10") (pin "5") (pinfunction "PAD_5") (pintype "passive"))
      (node (ref "U11") (pin "2") (pinfunction "GND_2") (pintype "passive"))
      (node (ref "U11") (pin "5") (pinfunction "PAD_5") (pintype "passive"))
      (node (ref "U12") (pin "2") (pinfunction "GND_2") (pintype "passive"))
      (node (ref "U12") (pin "5") (pinfunction "PAD_5") (pintype "passive"))
      (node (ref "U13") (pin "2") (pinfunction "GND_2") (pintype "passive"))
      (node (ref "U13") (pin "5") (pinfunction "PAD_5") (pintype "passive"))
      (node (ref "U14") (pin "2") (pinfunction "GND_2") (pintype "passive"))
      (node (ref "U14") (pin "5") (pinfunction "PAD_5") (pintype "passive"))
      (node (ref "U15") (pin "2") (pinfunction "GND_2") (pintype "passive"))
      (node (ref "U15") (pin "5") (pinfunction "PAD_5") (pintype "passive"))
      (node (ref "U16") (pin "2") (pinfunction "GND_2") (pintype "passive"))
      (node (ref "U16") (pin "5") (pinfunction "PAD_5") (pintype "passive"))
      (node (ref "U2") (pin "2") (pinfunction "GND_2") (pintype "passive"))
      (node (ref "U2") (pin "5") (pinfunction "PAD_5") (pintype "passive"))
      (node (ref "U3") (pin "2") (pinfunction "GND_2") (pintype "passive"))
      (node (ref "U3") (pin "5") (pinfunction "PAD_5") (pintype "passive"))
      (node (ref "U4") (pin "2") (pinfunction "GND_2") (pintype "passive"))
      (node (ref "U4") (pin "5") (pinfunction "PAD_5") (pintype "passive"))
      (node (ref "U5") (pin "2") (pinfunction "GND_2") (pintype "passive"))
      (node (ref "U5") (pin "5") (pinfunction "PAD_5") (pintype "passive"))
      (node (ref "U6") (pin "2") (pinfunction "GND_2") (pintype "passive"))
      (node (ref "U6") (pin "5") (pinfunction "PAD_5") (pintype "passive"))
      (node (ref "U7") (pin "4") (pinfunction "PGND_4") (pintype "passive"))
      (node (ref "U8") (pin "2") (pinfunction "GND_2") (pintype "passive"))
      (node (ref "U8") (pin "5") (pinfunction "PAD_5") (pintype "passive"))
      (node (ref "U9") (pin "2") (pinfunction "GND_2") (pintype "passive"))
      (node (ref "U9") (pin "5") (pinfunction "PAD_5") (pintype "passive"))
    )
    (net (code "59") (name "Net-(LED1-PadA)") (class "Default")
      (node (ref "LED1") (pin "A") (pinfunction "A_A") (pintype "passive"))
      (node (ref "R5") (pin "2") (pinfunction "2_2") (pintype "passive"))
    )
    (net (code "60") (name "Net-(LED2-PadA)") (class "Default")
      (node (ref "LED2") (pin "A") (pinfunction "A_A") (pintype "passive"))
      (node (ref "R3") (pin "2") (pinfunction "2_2") (pintype "passive"))
    )
    (net (code "61") (name "Net-(U7-BST)") (class "Default")
      (node (ref "C9") (pin "1") (pintype "passive"))
      (node (ref "U7") (pin "7") (pinfunction "BST_7") (pintype "passive"))
    )
    (net (code "62") (name "Net-(U7-FB)") (class "Default")
      (node (ref "C20") (pin "1") (pintype "passive"))
      (node (ref "R1") (pin "1") (pinfunction "1_1") (pintype "passive"))
      (node (ref "R2") (pin "2") (pinfunction "2_2") (pintype "passive"))
      (node (ref "U7") (pin "2") (pinfunction "FB_2") (pintype "passive"))
    )
    (net (code "63") (name "Net-(U7-SS)") (class "Default")
      (node (ref "C26") (pin "2") (pintype "passive"))
      (node (ref "U7") (pin "9") (pinfunction "SS_9") (pintype "passive"))
    )
    (net (code "64") (name "Net-(U7-SW)") (class "Default")
      (node (ref "C9") (pin "2") (pintype "passive"))
      (node (ref "L1") (pin "1") (pinfunction "1_1") (pintype "passive"))
      (node (ref "U7") (pin "8") (pinfunction "SW_8") (pintype "passive"))
    )
    (net (code "65") (name "Net-(U7-VCC)") (class "Default")
      (node (ref "C25") (pin "2") (pintype "passive"))
      (node (ref "U7") (pin "1") (pinfunction "VCC_1") (pintype "passive"))
    )
    (net (code "66") (name "VC") (class "Default")
      (node (ref "C18") (pin "1") (pintype "passive"))
      (node (ref "C19") (pin "2") (pintype "passive"))
      (node (ref "J14") (pin "1") (pinfunction "1_1") (pintype "passive"))
      (node (ref "U7") (pin "5") (pinfunction "VIN_5") (pintype "passive"))
      (node (ref "U7") (pin "6") (pinfunction "VIN_6") (pintype "passive"))
    )
    (net (code "67") (name "unconnected-(J10-Pad11)") (class "Default")
      (node (ref "J10") (pin "11") (pinfunction "11_11") (pintype "passive"))
    )
    (net (code "68") (name "unconnected-(J13-PadSH)") (class "Default")
      (node (ref "J13") (pin "SH") (pinfunction "SH_SH") (pintype "passive"))
    )
    (net (code "69") (name "unconnected-(U1-VBAT-Pad1)") (class "Default")
      (node (ref "U1") (pin "1") (pinfunction "VBAT_1") (pintype "passive"))
    )
    (net (code "70") (name "unconnected-(U1-VDDA-Pad21)") (class "Default")
      (node (ref "U1") (pin "21") (pinfunction "VDDA_21") (pintype "passive"))
    )
    (net (code "71") (name "unconnected-(U1-VREF+-Pad20)") (class "Default")
      (node (ref "U1") (pin "20") (pinfunction "VREF+_20") (pintype "passive"))
    )
    (net (code "72") (name "unconnected-(U7-EN-Pad3)") (class "Default")
      (node (ref "U7") (pin "3") (pinfunction "EN_3") (pintype "passive"))
    )
  )
)
